# Trafo.net
KiCad netlist of a schematic drawn in Altium Designer
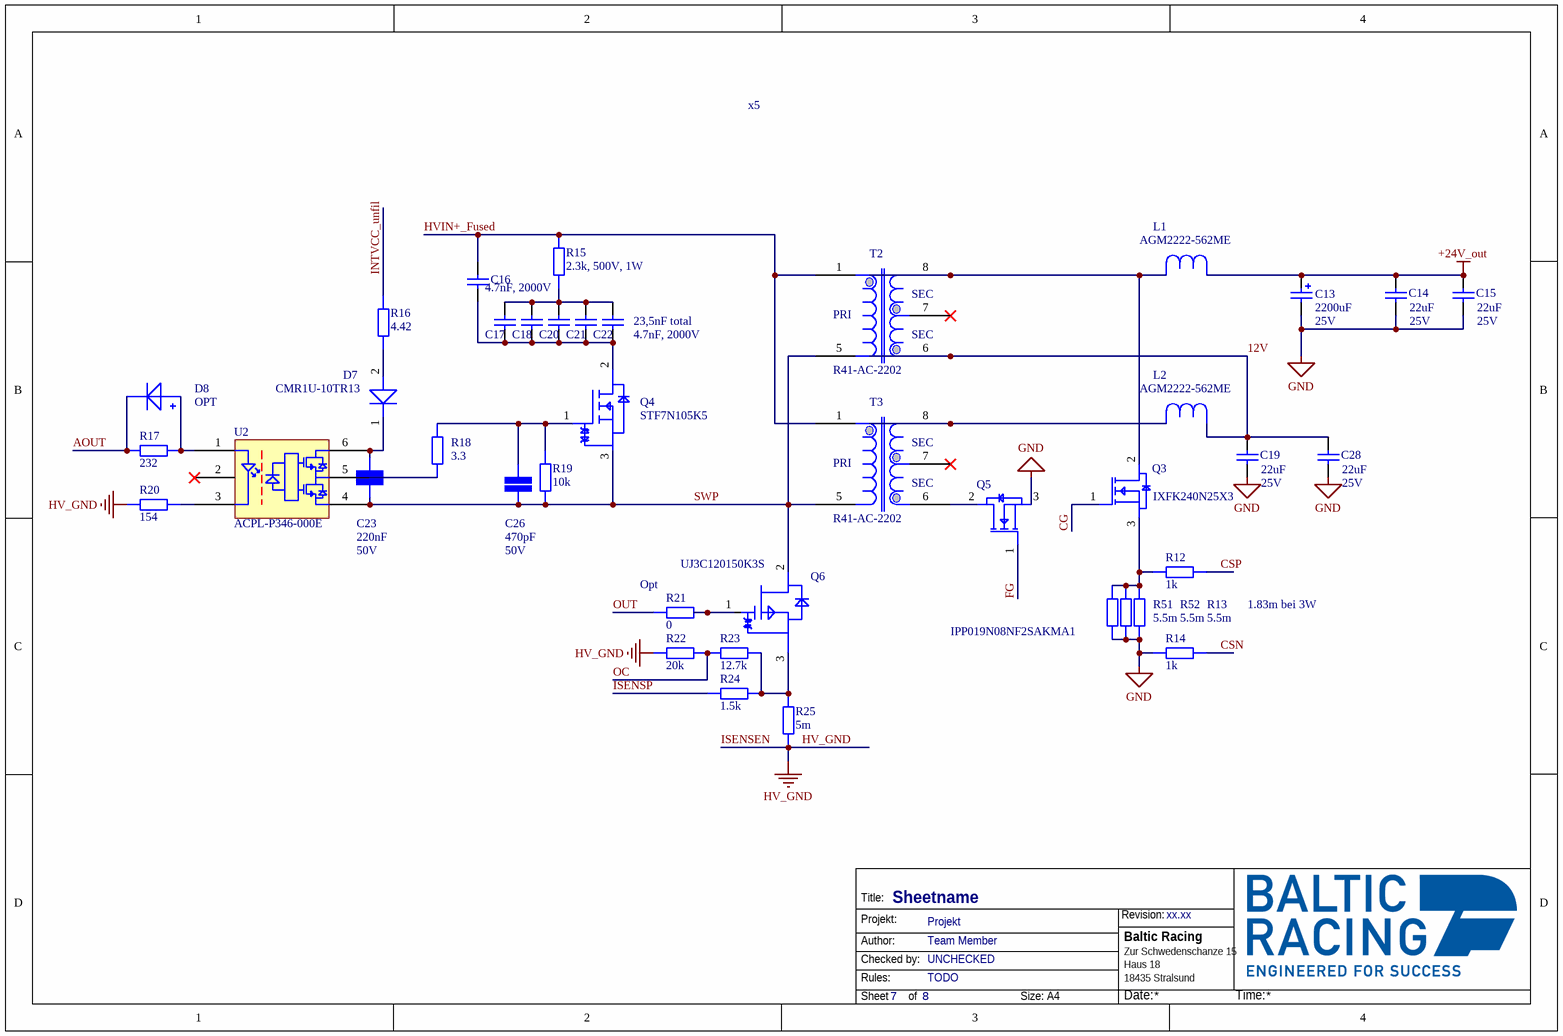
[diagram p0: Trafo.SchDoc]

(export (version "E")
  (design (tool "Eeschema 10.0.6"))
  (components
    (comp (ref "C13")
      (value "~")
      (footprint "WCAP-ATG8_D13H25")
      (description "WCAP-ATG8 Aluminum Electrolytic Capacitor, Radial, THT, D13xH25, 2200uF, 25V")
      (fields
        (field (name "MANUFACTURER PART NUMBER") "860010478021")
        (field (name "MANUFACTURER") "Wurth Elektronik")
        (field (name "CAPACITANCE") "2200uF")
        (field (name "VOLTAGE") "25V")
      )
      (libsource (lib "Altium_WCAP-ATG8 (rev20b)") (part "860010478021"))
    )
    (comp (ref "C14")
      (value "~")
      (footprint "WCAP-CSGP_1210_H=2.5mm")
      (description "WCAP-CSGP Multilayer Ceramic Chip Capacitor, General Purpose, size 1210, X5R, 22uF, 25V")
      (fields
        (field (name "MANUFACTURER PART NUMBER") "885012109014")
        (field (name "MANUFACTURER") "Wurth Elektronik")
        (field (name "CAPACITANCE") "22uF")
        (field (name "VOLTAGE") "25V")
      )
      (libsource (lib "Altium_WCAP-CSGP (rev21d)") (part "885012109014"))
    )
    (comp (ref "C15")
      (value "~")
      (footprint "WCAP-CSGP_1210_H=2.5mm")
      (description "WCAP-CSGP Multilayer Ceramic Chip Capacitor, General Purpose, size 1210, X5R, 22uF, 25V")
      (fields
        (field (name "MANUFACTURER PART NUMBER") "885012109014")
        (field (name "MANUFACTURER") "Wurth Elektronik")
        (field (name "CAPACITANCE") "22uF")
        (field (name "VOLTAGE") "25V")
      )
      (libsource (lib "Altium_WCAP-CSGP (rev21d)") (part "885012109014"))
    )
    (comp (ref "C16")
      (value "4.7nF, 2000V")
      (footprint "WCAP-CSMH_1812_H2")
      (description "WCAP-CSMH Multilayer Ceramic Chip Capacitor, size 1812, X7R Class II, 4.7nF, 2000V")
      (fields
        (field (name "MANUFACTURER PART NUMBER") "885342211008")
        (field (name "MANUFACTURER") "Wurth Elektronik")
      )
      (libsource (lib "Altium_WCAP-CSMH (rev20a)") (part "885342211008"))
    )
    (comp (ref "C17")
      (value "4.7nF, 2000V")
      (footprint "WCAP-CSMH_1812_H2")
      (description "WCAP-CSMH Multilayer Ceramic Chip Capacitor, size 1812, X7R Class II, 4.7nF, 2000V")
      (fields
        (field (name "MANUFACTURER PART NUMBER") "885342211008")
        (field (name "MANUFACTURER") "Wurth Elektronik")
      )
      (libsource (lib "Altium_WCAP-CSMH (rev20a)") (part "885342211008"))
    )
    (comp (ref "C18")
      (value "4.7nF, 2000V")
      (footprint "WCAP-CSMH_1812_H2")
      (description "WCAP-CSMH Multilayer Ceramic Chip Capacitor, size 1812, X7R Class II, 4.7nF, 2000V")
      (fields
        (field (name "MANUFACTURER PART NUMBER") "885342211008")
        (field (name "MANUFACTURER") "Wurth Elektronik")
      )
      (libsource (lib "Altium_WCAP-CSMH (rev20a)") (part "885342211008"))
    )
    (comp (ref "C19")
      (value "~")
      (footprint "WCAP-CSGP_1210_H=2.5mm")
      (description "WCAP-CSGP Multilayer Ceramic Chip Capacitor, General Purpose, size 1210, X5R, 22uF, 25V")
      (fields
        (field (name "MANUFACTURER PART NUMBER") "885012109014")
        (field (name "MANUFACTURER") "Wurth Elektronik")
        (field (name "CAPACITANCE") "22uF")
        (field (name "VOLTAGE") "25V")
      )
      (libsource (lib "Altium_WCAP-CSGP (rev21d)") (part "885012109014"))
    )
    (comp (ref "C20")
      (value "4.7nF, 2000V")
      (footprint "WCAP-CSMH_1812_H2")
      (description "WCAP-CSMH Multilayer Ceramic Chip Capacitor, size 1812, X7R Class II, 4.7nF, 2000V")
      (fields
        (field (name "MANUFACTURER PART NUMBER") "885342211008")
        (field (name "MANUFACTURER") "Wurth Elektronik")
      )
      (libsource (lib "Altium_WCAP-CSMH (rev20a)") (part "885342211008"))
    )
    (comp (ref "C21")
      (value "4.7nF, 2000V")
      (footprint "WCAP-CSMH_1812_H2")
      (description "WCAP-CSMH Multilayer Ceramic Chip Capacitor, size 1812, X7R Class II, 4.7nF, 2000V")
      (fields
        (field (name "MANUFACTURER PART NUMBER") "885342211008")
        (field (name "MANUFACTURER") "Wurth Elektronik")
      )
      (libsource (lib "Altium_WCAP-CSMH (rev20a)") (part "885342211008"))
    )
    (comp (ref "C22")
      (value "4.7nF, 2000V")
      (footprint "WCAP-CSMH_1812_H2")
      (description "WCAP-CSMH Multilayer Ceramic Chip Capacitor, size 1812, X7R Class II, 4.7nF, 2000V")
      (fields
        (field (name "MANUFACTURER PART NUMBER") "885342211008")
        (field (name "MANUFACTURER") "Wurth Elektronik")
      )
      (libsource (lib "Altium_WCAP-CSMH (rev20a)") (part "885342211008"))
    )
    (comp (ref "C23")
      (value "220nF")
      (footprint "CAP 1206/3216")
      (description "Capacitor with multiple Footprints")
      (fields (field (name "VOLTAGE") "50V") (field (name "Comment") "SMD Capacitor"))
      (libsource (lib "Standardbauteile") (part "SMD Capacitor"))
    )
    (comp (ref "C26")
      (value "470pF")
      (footprint "CAP 1206/3216")
      (description "Capacitor with multiple Footprints")
      (fields (field (name "VOLTAGE") "50V") (field (name "Comment") "SMD Capacitor"))
      (libsource (lib "Standardbauteile") (part "SMD Capacitor"))
    )
    (comp (ref "C28")
      (value "~")
      (footprint "WCAP-CSGP_1210_H=2.5mm")
      (description "WCAP-CSGP Multilayer Ceramic Chip Capacitor, General Purpose, size 1210, X5R, 22uF, 25V")
      (fields
        (field (name "MANUFACTURER PART NUMBER") "885012109014")
        (field (name "MANUFACTURER") "Wurth Elektronik")
        (field (name "CAPACITANCE") "22uF")
        (field (name "VOLTAGE") "25V")
      )
      (libsource (lib "Altium_WCAP-CSGP (rev21d)") (part "885012109014"))
    )
    (comp (ref "D7")
      (value "CMR1U-10TR13")
      (footprint "DIOC4536X24L CMR1U-10")
      (description "Silicon Ultra Fast Recovery Rectifier 1000V 30A 2-Pin SMB Surface Mount T/R")
      (fields (field (name "MANUFACTURER") "Central Semiconductor"))
      (libsource (lib "Integrated_LibraryLukas_New") (part "CMR1U-10TR13"))
    )
    (comp (ref "D8")
      (value "OPT")
      (footprint "DIOM2715X18N")
      (libsource (lib "Integrated_LibraryLukas_New") (part "BAT46WH"))
    )
    (comp (ref "L1")
      (value "AGM2222-562ME")
      (footprint "AGM2222-562")
      (description "Shielded Power Inductors")
      (libsource (lib "Integrated_LibraryLukas_New") (part "AGM2222-562ME"))
    )
    (comp (ref "L2")
      (value "AGM2222-562ME")
      (footprint "AGM2222-562")
      (description "Shielded Power Inductors")
      (libsource (lib "Integrated_LibraryLukas_New") (part "AGM2222-562ME"))
    )
    (comp (ref "Q3")
      (value "IXFK240N25X3")
      (footprint "IXFK240N25X3_w_Cooler")
      (description "Mosfet N-ch 250V 240A TO264")
      (fields (field (name "MANUFACTURER") "IXYS"))
      (libsource (lib "Integrated_LibraryLukas_New") (part "IXFK240N25X3"))
    )
    (comp (ref "Q4")
      (value "STF7N105K5")
      (footprint "TO-220-3")
      (description "N-channel 1050 V, 1.4 Ohm typ., 4 A MDmesh K5 Power MOSFETs in TO-220FP package")
      (fields (field (name "MANUFACTURER") "STMicroelectronics"))
      (libsource (lib "Integrated_LibraryLukas_New") (part "STF7N105K5"))
    )
    (comp (ref "Q5")
      (value "IPP019N08NF2SAKMA1")
      (footprint "IPP019N08NF2SAKMA1_w_Cooler")
      (description "Transistor Power MOSFET N-Channel 80V 191A 3-Pin TO-220 Tube")
      (fields (field (name "MANUFACTURER") "Infineon"))
      (libsource (lib "Integrated_LibraryLukas_New") (part "IPP019N08NF2SAKMA1"))
    )
    (comp (ref "Q6")
      (value "UJ3C120150K3S")
      (footprint "UJ3C120150K3S_w_Cooler")
      (description "Sicfet N-ch 1200V 18.4A TO247-3")
      (fields (field (name "MANUFACTURER") "UnitedSiC"))
      (libsource (lib "Integrated_LibraryLukas_New") (part "UJ3C120150K3S"))
    )
    (comp (ref "R12")
      (value "1k")
      (footprint "STACKPOLE CSR1206")
      (description "Resistor with multiple footprints")
      (fields (field (name "Comment") "SMD Resistor"))
      (libsource (lib "Standardbauteile") (part "SMD Resistor"))
    )
    (comp (ref "R13")
      (value "5.5m")
      (footprint "STACKPOLE CSR1206")
      (description "Resistor with multiple footprints")
      (libsource (lib "Standardbauteile") (part "SMD Resistor"))
    )
    (comp (ref "R14")
      (value "1k")
      (footprint "STACKPOLE CSR1206")
      (description "Resistor with multiple footprints")
      (fields (field (name "Comment") "SMD Resistor"))
      (libsource (lib "Standardbauteile") (part "SMD Resistor"))
    )
    (comp (ref "R15")
      (value "2.3k, 500V, 1W")
      (footprint "STACKPOLE CSRN2512")
      (description "Resistor with multiple footprints")
      (fields (field (name "Comment") "CRCW25122K20FKEG"))
      (libsource (lib "Standardbauteile") (part "SMD Resistor"))
    )
    (comp (ref "R16")
      (value "4.42")
      (footprint "STACKPOLE CSR0603")
      (description "Resistor with multiple footprints")
      (fields (field (name "Comment") "SMD Resistor"))
      (libsource (lib "Standardbauteile") (part "SMD Resistor"))
    )
    (comp (ref "R17")
      (value "232")
      (footprint "STACKPOLE CSR1206")
      (description "Resistor with multiple footprints")
      (fields (field (name "Comment") "SMD Resistor"))
      (libsource (lib "Standardbauteile") (part "SMD Resistor"))
    )
    (comp (ref "R18")
      (value "3.3")
      (footprint "STACKPOLE CSR0603")
      (description "Resistor with multiple footprints")
      (fields (field (name "Comment") "SMD Resistor"))
      (libsource (lib "Standardbauteile") (part "SMD Resistor"))
    )
    (comp (ref "R19")
      (value "10k")
      (footprint "STACKPOLE CSR0603")
      (description "Resistor with multiple footprints")
      (fields (field (name "Comment") "SMD Resistor"))
      (libsource (lib "Standardbauteile") (part "SMD Resistor"))
    )
    (comp (ref "R20")
      (value "154")
      (footprint "STACKPOLE CSR1206")
      (description "Resistor with multiple footprints")
      (fields (field (name "Comment") "SMD Resistor"))
      (libsource (lib "Standardbauteile") (part "SMD Resistor"))
    )
    (comp (ref "R21")
      (value "0")
      (footprint "STACKPOLE CSR0603")
      (description "Resistor with multiple footprints")
      (fields (field (name "Comment") "SMD Resistor"))
      (libsource (lib "Standardbauteile") (part "SMD Resistor"))
    )
    (comp (ref "R22")
      (value "20k")
      (footprint "STACKPOLE CSR0603")
      (description "Resistor with multiple footprints")
      (fields (field (name "Comment") "SMD Resistor"))
      (libsource (lib "Standardbauteile") (part "SMD Resistor"))
    )
    (comp (ref "R23")
      (value "12.7k")
      (footprint "STACKPOLE CSR0603")
      (description "Resistor with multiple footprints")
      (fields (field (name "Comment") "SMD Resistor"))
      (libsource (lib "Standardbauteile") (part "SMD Resistor"))
    )
    (comp (ref "R24")
      (value "1.5k")
      (footprint "STACKPOLE CSR0603")
      (description "Resistor with multiple footprints")
      (fields (field (name "Comment") "SMD Resistor"))
      (libsource (lib "Standardbauteile") (part "SMD Resistor"))
    )
    (comp (ref "R25")
      (value "5m")
      (footprint "STACKPOLE CSR1206")
      (description "Resistor with multiple footprints")
      (fields (field (name "Comment") "ULR1S-R0055FT2"))
      (libsource (lib "Standardbauteile") (part "SMD Resistor"))
    )
    (comp (ref "R51")
      (value "5.5m")
      (footprint "STACKPOLE CSR1206")
      (description "Resistor with multiple footprints")
      (libsource (lib "Standardbauteile") (part "SMD Resistor"))
    )
    (comp (ref "R52")
      (value "5.5m")
      (footprint "STACKPOLE CSR1206")
      (description "Resistor with multiple footprints")
      (libsource (lib "Standardbauteile") (part "SMD Resistor"))
    )
    (comp (ref "T2")
      (value "R41-AC-2202")
      (footprint "R41-AC-2202 Landing Pattern")
      (description "High Voltage Transformer")
      (libsource (lib "Integrated_LibraryLukas_New") (part "R41-AC-2202"))
    )
    (comp (ref "T3")
      (value "R41-AC-2202")
      (footprint "R41-AC-2202 Landing Pattern")
      (description "High Voltage Transformer")
      (libsource (lib "Integrated_LibraryLukas_New") (part "R41-AC-2202"))
    )
    (comp (ref "U2")
      (value "ACPL-P346-000E")
      (footprint "SOP-6 Stretched")
      (description "Logic IC Output Optocoupler, 1-Element, 3750V Isolation")
      (fields (field (name "MANUFACTURER") "Broadcom Avago"))
      (libsource (lib "Integrated_LibraryLukas_New") (part "ACPL-P346-000E"))
    )
  )
  (nets
    (net (code "1") (name "+24V_out") (class "Default")
      (node (ref "C13") (pin "1") (pinfunction "P_1") (pintype "passive"))
      (node (ref "C14") (pin "1") (pinfunction "1_1") (pintype "passive"))
      (node (ref "C15") (pin "1") (pinfunction "1_1") (pintype "passive"))
      (node (ref "L1") (pin "2") (pintype "passive"))
    )
    (net (code "2") (name "/12V") (class "Default")
      (node (ref "C19") (pin "1") (pinfunction "1_1") (pintype "passive"))
      (node (ref "C28") (pin "1") (pinfunction "1_1") (pintype "passive"))
      (node (ref "L2") (pin "2") (pintype "passive"))
      (node (ref "T2") (pin "6") (pintype "passive"))
    )
    (net (code "3") (name "/AOUT") (class "Default")
      (node (ref "D8") (pin "2") (pintype "passive"))
      (node (ref "R17") (pin "1") (pinfunction "1_1") (pintype "passive"))
    )
    (net (code "4") (name "/CG") (class "Default") (node (ref "Q3") (pin "1") (pintype "input")))
    (net (code "5") (name "/CSN") (class "Default")
      (node (ref "R14") (pin "2") (pinfunction "2_2") (pintype "passive"))
    )
    (net (code "6") (name "/CSP") (class "Default")
      (node (ref "R12") (pin "2") (pinfunction "2_2") (pintype "passive"))
    )
    (net (code "7") (name "/FG") (class "Default") (node (ref "Q5") (pin "1") (pintype "input")))
    (net (code "8") (name "/HVIN+_Fused") (class "Default")
      (node (ref "C16") (pin "1") (pinfunction "1_1") (pintype "passive"))
      (node (ref "R15") (pin "2") (pinfunction "2_2") (pintype "passive"))
      (node (ref "T2") (pin "1") (pintype "passive"))
      (node (ref "T3") (pin "1") (pintype "passive"))
    )
    (net (code "9") (name "/INTVCC_unfil") (class "Default")
      (node (ref "R16") (pin "2") (pinfunction "2_2") (pintype "passive"))
    )
    (net (code "10") (name "/ISENSP") (class "Default")
      (node (ref "R24") (pin "1") (pinfunction "1_1") (pintype "passive"))
    )
    (net (code "11") (name "/OC") (class "Default")
      (node (ref "R22") (pin "2") (pinfunction "2_2") (pintype "passive"))
      (node (ref "R23") (pin "1") (pinfunction "1_1") (pintype "passive"))
    )
    (net (code "12") (name "/OUT") (class "Default")
      (node (ref "R21") (pin "1") (pinfunction "1_1") (pintype "passive"))
    )
    (net (code "13") (name "/SWP") (class "Default")
      (node (ref "C23") (pin "2") (pinfunction "2_2") (pintype "passive"))
      (node (ref "C26") (pin "2") (pinfunction "2_2") (pintype "passive"))
      (node (ref "Q4") (pin "3") (pintype "passive"))
      (node (ref "Q6") (pin "2") (pintype "passive"))
      (node (ref "R19") (pin "1") (pinfunction "1_1") (pintype "passive"))
      (node (ref "T2") (pin "5") (pintype "passive"))
      (node (ref "T3") (pin "5") (pintype "passive"))
      (node (ref "U2") (pin "4") (pintype "passive"))
    )
    (net (code "14") (name "GND") (class "Default")
      (node (ref "C13") (pin "2") (pinfunction "N_2") (pintype "passive"))
      (node (ref "C14") (pin "2") (pinfunction "2_2") (pintype "passive"))
      (node (ref "C15") (pin "2") (pinfunction "2_2") (pintype "passive"))
      (node (ref "C19") (pin "2") (pinfunction "2_2") (pintype "passive"))
      (node (ref "C28") (pin "2") (pinfunction "2_2") (pintype "passive"))
      (node (ref "Q5") (pin "3") (pintype "input"))
      (node (ref "R13") (pin "1") (pinfunction "1_1") (pintype "passive"))
      (node (ref "R14") (pin "1") (pinfunction "1_1") (pintype "passive"))
      (node (ref "R51") (pin "1") (pinfunction "1_1") (pintype "passive"))
      (node (ref "R52") (pin "1") (pinfunction "1_1") (pintype "passive"))
    )
    (net (code "15") (name "HV_GND") (class "Default")
      (node (ref "R20") (pin "1") (pinfunction "1_1") (pintype "passive"))
      (node (ref "R22") (pin "1") (pinfunction "1_1") (pintype "passive"))
      (node (ref "R25") (pin "2") (pinfunction "2_2") (pintype "passive"))
    )
    (net (code "16") (name "Net-(C16-Pad2)") (class "Default")
      (node (ref "C16") (pin "2") (pinfunction "2_2") (pintype "passive"))
      (node (ref "C17") (pin "2") (pinfunction "2_2") (pintype "passive"))
      (node (ref "C18") (pin "2") (pinfunction "2_2") (pintype "passive"))
      (node (ref "C20") (pin "2") (pinfunction "2_2") (pintype "passive"))
      (node (ref "C21") (pin "2") (pinfunction "2_2") (pintype "passive"))
      (node (ref "C22") (pin "2") (pinfunction "2_2") (pintype "passive"))
      (node (ref "Q4") (pin "2") (pintype "passive"))
    )
    (net (code "17") (name "Net-(C17-Pad1)") (class "Default")
      (node (ref "C17") (pin "1") (pinfunction "1_1") (pintype "passive"))
      (node (ref "C18") (pin "1") (pinfunction "1_1") (pintype "passive"))
      (node (ref "C20") (pin "1") (pinfunction "1_1") (pintype "passive"))
      (node (ref "C21") (pin "1") (pinfunction "1_1") (pintype "passive"))
      (node (ref "C22") (pin "1") (pinfunction "1_1") (pintype "passive"))
      (node (ref "R15") (pin "1") (pinfunction "1_1") (pintype "passive"))
    )
    (net (code "18") (name "Net-(C23-Pad1)") (class "Default")
      (node (ref "C23") (pin "1") (pinfunction "1_1") (pintype "passive"))
      (node (ref "D7") (pin "1") (pintype "passive"))
      (node (ref "U2") (pin "6") (pintype "passive"))
    )
    (net (code "19") (name "Net-(C26-Pad1)") (class "Default")
      (node (ref "C26") (pin "1") (pinfunction "1_1") (pintype "passive"))
      (node (ref "Q4") (pin "1") (pintype "passive"))
      (node (ref "R18") (pin "2") (pinfunction "2_2") (pintype "passive"))
      (node (ref "R19") (pin "2") (pinfunction "2_2") (pintype "passive"))
    )
    (net (code "20") (name "Net-(D7-Pad2)") (class "Default")
      (node (ref "D7") (pin "2") (pintype "passive"))
      (node (ref "R16") (pin "1") (pinfunction "1_1") (pintype "passive"))
    )
    (net (code "21") (name "Net-(D8-Pad1)") (class "Default")
      (node (ref "D8") (pin "1") (pintype "passive"))
      (node (ref "R17") (pin "2") (pinfunction "2_2") (pintype "passive"))
      (node (ref "U2") (pin "1") (pintype "passive"))
    )
    (net (code "22") (name "Net-(L1-Pad1)") (class "Default")
      (node (ref "L1") (pin "1") (pintype "passive"))
      (node (ref "Q3") (pin "2") (pintype "input"))
      (node (ref "T2") (pin "8") (pintype "passive"))
    )
    (net (code "23") (name "Net-(L2-Pad1)") (class "Default")
      (node (ref "L2") (pin "1") (pintype "passive"))
      (node (ref "T3") (pin "8") (pintype "passive"))
    )
    (net (code "24") (name "Net-(Q3-Pad3)") (class "Default")
      (node (ref "Q3") (pin "3") (pintype "input"))
      (node (ref "R12") (pin "1") (pinfunction "1_1") (pintype "passive"))
      (node (ref "R13") (pin "2") (pinfunction "2_2") (pintype "passive"))
      (node (ref "R51") (pin "2") (pinfunction "2_2") (pintype "passive"))
      (node (ref "R52") (pin "2") (pinfunction "2_2") (pintype "passive"))
    )
    (net (code "25") (name "Net-(Q5-Pad2)") (class "Default")
      (node (ref "Q5") (pin "2") (pintype "input"))
      (node (ref "T3") (pin "6") (pintype "passive"))
    )
    (net (code "26") (name "Net-(Q6-Pad1)") (class "Default")
      (node (ref "Q6") (pin "1") (pintype "passive"))
      (node (ref "R21") (pin "2") (pinfunction "2_2") (pintype "passive"))
    )
    (net (code "27") (name "Net-(Q6-Pad3)") (class "Default")
      (node (ref "Q6") (pin "3") (pintype "passive"))
      (node (ref "R23") (pin "2") (pinfunction "2_2") (pintype "passive"))
      (node (ref "R24") (pin "2") (pinfunction "2_2") (pintype "passive"))
      (node (ref "R25") (pin "1") (pinfunction "1_1") (pintype "passive"))
    )
    (net (code "28") (name "Net-(R18-Pad1)") (class "Default")
      (node (ref "R18") (pin "1") (pinfunction "1_1") (pintype "passive"))
      (node (ref "U2") (pin "5") (pintype "passive"))
    )
    (net (code "29") (name "Net-(R20-Pad2)") (class "Default")
      (node (ref "R20") (pin "2") (pinfunction "2_2") (pintype "passive"))
      (node (ref "U2") (pin "3") (pintype "passive"))
    )
    (net (code "30") (name "unconnected-(T2-Pad7)") (class "Default")
      (node (ref "T2") (pin "7") (pintype "passive+no_connect"))
    )
    (net (code "31") (name "unconnected-(T3-Pad7)") (class "Default")
      (node (ref "T3") (pin "7") (pintype "passive+no_connect"))
    )
    (net (code "32") (name "unconnected-(U2-Pad2)") (class "Default")
      (node (ref "U2") (pin "2") (pintype "passive+no_connect"))
    )
  )
)
